# Spolerigg1.net
KiCad netlist of a schematic drawn in Altium Designer
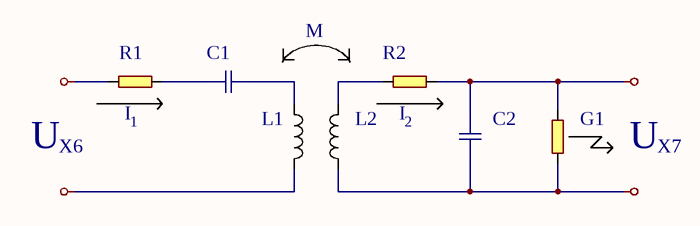
[diagram p0: Spolerigg1.SchDoc]

(export (version "E")
  (design (tool "Eeschema 10.0.6"))
  (components
    (comp (ref "C1")
      (value "PC/HV/S/WF 22NF")
      (footprint "CAPAD340W1L280D11B")
      (description "CAP, FILM, PP, 22NF, 1.5KV, AXIAL")
      (libsource (lib "OVLib") (part "CAP"))
    )
    (comp (ref "C2")
      (value "PC/HV/S/WF 22NF")
      (footprint "CAPAD340W1L280D11B")
      (description "CAP, FILM, PP, 22NF, 1.5KV, AXIAL")
      (libsource (lib "OVLib") (part "CAP"))
    )
    (comp (ref "G1")
      (value "1.0")
      (footprint "RESA_0.25W")
      (description "0.25W 1% Generic resistor")
      (libsource (lib "") (part "Resistor2_1"))
    )
    (comp (ref "L1")
      (value "SMD spoler")
      (footprint "INDP3225X20N")
      (description "SMD inductors og tomme SMD bokser")
      (libsource (lib "OVLib") (part "IND_GENERIC"))
    )
    (comp (ref "L2")
      (value "SMD spoler")
      (footprint "INDP3225X20N")
      (description "SMD inductors og tomme SMD bokser")
      (libsource (lib "OVLib") (part "IND_GENERIC"))
    )
    (comp (ref "R1")
      (value "1.0")
      (footprint "RESA_0.25W")
      (description "0.25W 1% Generic resistor")
      (libsource (lib "OVLib") (part "Resistor2"))
    )
    (comp (ref "R2")
      (value "1.0")
      (footprint "RESA_0.25W")
      (description "0.25W 1% Generic resistor")
      (libsource (lib "OVLib") (part "Resistor2"))
    )
  )
  (nets
    (net (code "1") (name "GND") (class "Default")
      (node (ref "C2") (pin "1") (pinfunction "1_1") (pintype "passive"))
      (node (ref "G1") (pin "1") (pinfunction "1_1") (pintype "passive"))
      (node (ref "L1") (pin "2") (pinfunction "2_2") (pintype "passive"))
      (node (ref "L2") (pin "1") (pinfunction "1_1") (pintype "passive"))
    )
    (net (code "2") (name "IN") (class "Default")
      (node (ref "R1") (pin "1") (pinfunction "1_1") (pintype "passive"))
    )
    (net (code "3") (name "Net-(C1-Pad1)") (class "Default")
      (node (ref "C1") (pin "1") (pinfunction "1_1") (pintype "passive"))
      (node (ref "R1") (pin "2") (pinfunction "2_2") (pintype "passive"))
    )
    (net (code "4") (name "Net-(C1-Pad2)") (class "Default")
      (node (ref "C1") (pin "2") (pinfunction "2_2") (pintype "passive"))
      (node (ref "L1") (pin "1") (pinfunction "1_1") (pintype "passive"))
    )
    (net (code "5") (name "Net-(L2-Pad2)") (class "Default")
      (node (ref "L2") (pin "2") (pinfunction "2_2") (pintype "passive"))
      (node (ref "R2") (pin "1") (pinfunction "1_1") (pintype "passive"))
    )
    (net (code "6") (name "OUT") (class "Default")
      (node (ref "C2") (pin "2") (pinfunction "2_2") (pintype "passive"))
      (node (ref "G1") (pin "2") (pinfunction "2_2") (pintype "passive"))
      (node (ref "R2") (pin "2") (pinfunction "2_2") (pintype "passive"))
    )
  )
)
